# PCB_0015.net
KiCad netlist of a schematic drawn in EAGLE
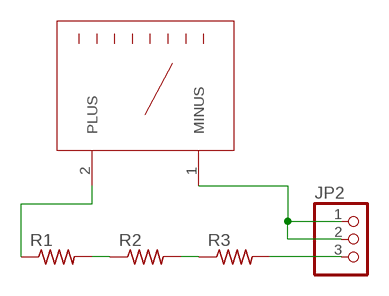
[diagram p0: schematic, sheet 1]

(export (version "E")
  (design (tool "Eeschema 10.0.6"))
  (components
    (comp (ref "JP2")
      (value "PINHD-1X3")
      (footprint "eagle-import:1X03")
      (libsource (lib "eagle-import") (part "PINHD-1X3"))
    )
    (comp (ref "R1")
      (value "R-US_R0603")
      (footprint "eagle-import:R0603")
      (libsource (lib "eagle-import") (part "R-US_R0603"))
    )
    (comp (ref "R2")
      (value "R-US_R0603")
      (footprint "eagle-import:R0603")
      (libsource (lib "eagle-import") (part "R-US_R0603"))
    )
    (comp (ref "R3")
      (value "R-US_R0603")
      (footprint "eagle-import:R0603")
      (libsource (lib "eagle-import") (part "R-US_R0603"))
    )
    (comp (ref "U$1")
      (value "METER")
      (footprint "eagle-import:METER_85C1")
      (libsource (lib "eagle-import") (part "METER"))
    )
  )
  (nets
    (net (code "1") (name "Net-(JP2-Pad3)") (class "Default")
      (node (ref "JP2") (pin "3") (pinfunction "3_3") (pintype "passive"))
      (node (ref "R3") (pin "2") (pinfunction "2_2") (pintype "passive"))
    )
    (net (code "2") (name "Net-(R1-Pad2)") (class "Default")
      (node (ref "R1") (pin "2") (pinfunction "2_2") (pintype "passive"))
      (node (ref "R2") (pin "1") (pinfunction "1_1") (pintype "passive"))
    )
    (net (code "3") (name "Net-(R2-Pad2)") (class "Default")
      (node (ref "R2") (pin "2") (pinfunction "2_2") (pintype "passive"))
      (node (ref "R3") (pin "1") (pinfunction "1_1") (pintype "passive"))
    )
    (net (code "4") (name "Net-(U$1-MINUS)") (class "Default")
      (node (ref "JP2") (pin "1") (pinfunction "1_1") (pintype "passive"))
      (node (ref "JP2") (pin "2") (pinfunction "2_2") (pintype "passive"))
      (node (ref "U$1") (pin "1") (pinfunction "MINUS_1") (pintype "bidirectional"))
    )
    (net (code "5") (name "Net-(U$1-PLUS)") (class "Default")
      (node (ref "R1") (pin "1") (pinfunction "1_1") (pintype "passive"))
      (node (ref "U$1") (pin "2") (pinfunction "PLUS_2") (pintype "bidirectional"))
    )
  )
)
